# Reader.net
KiCad netlist of a schematic drawn in Altium Designer
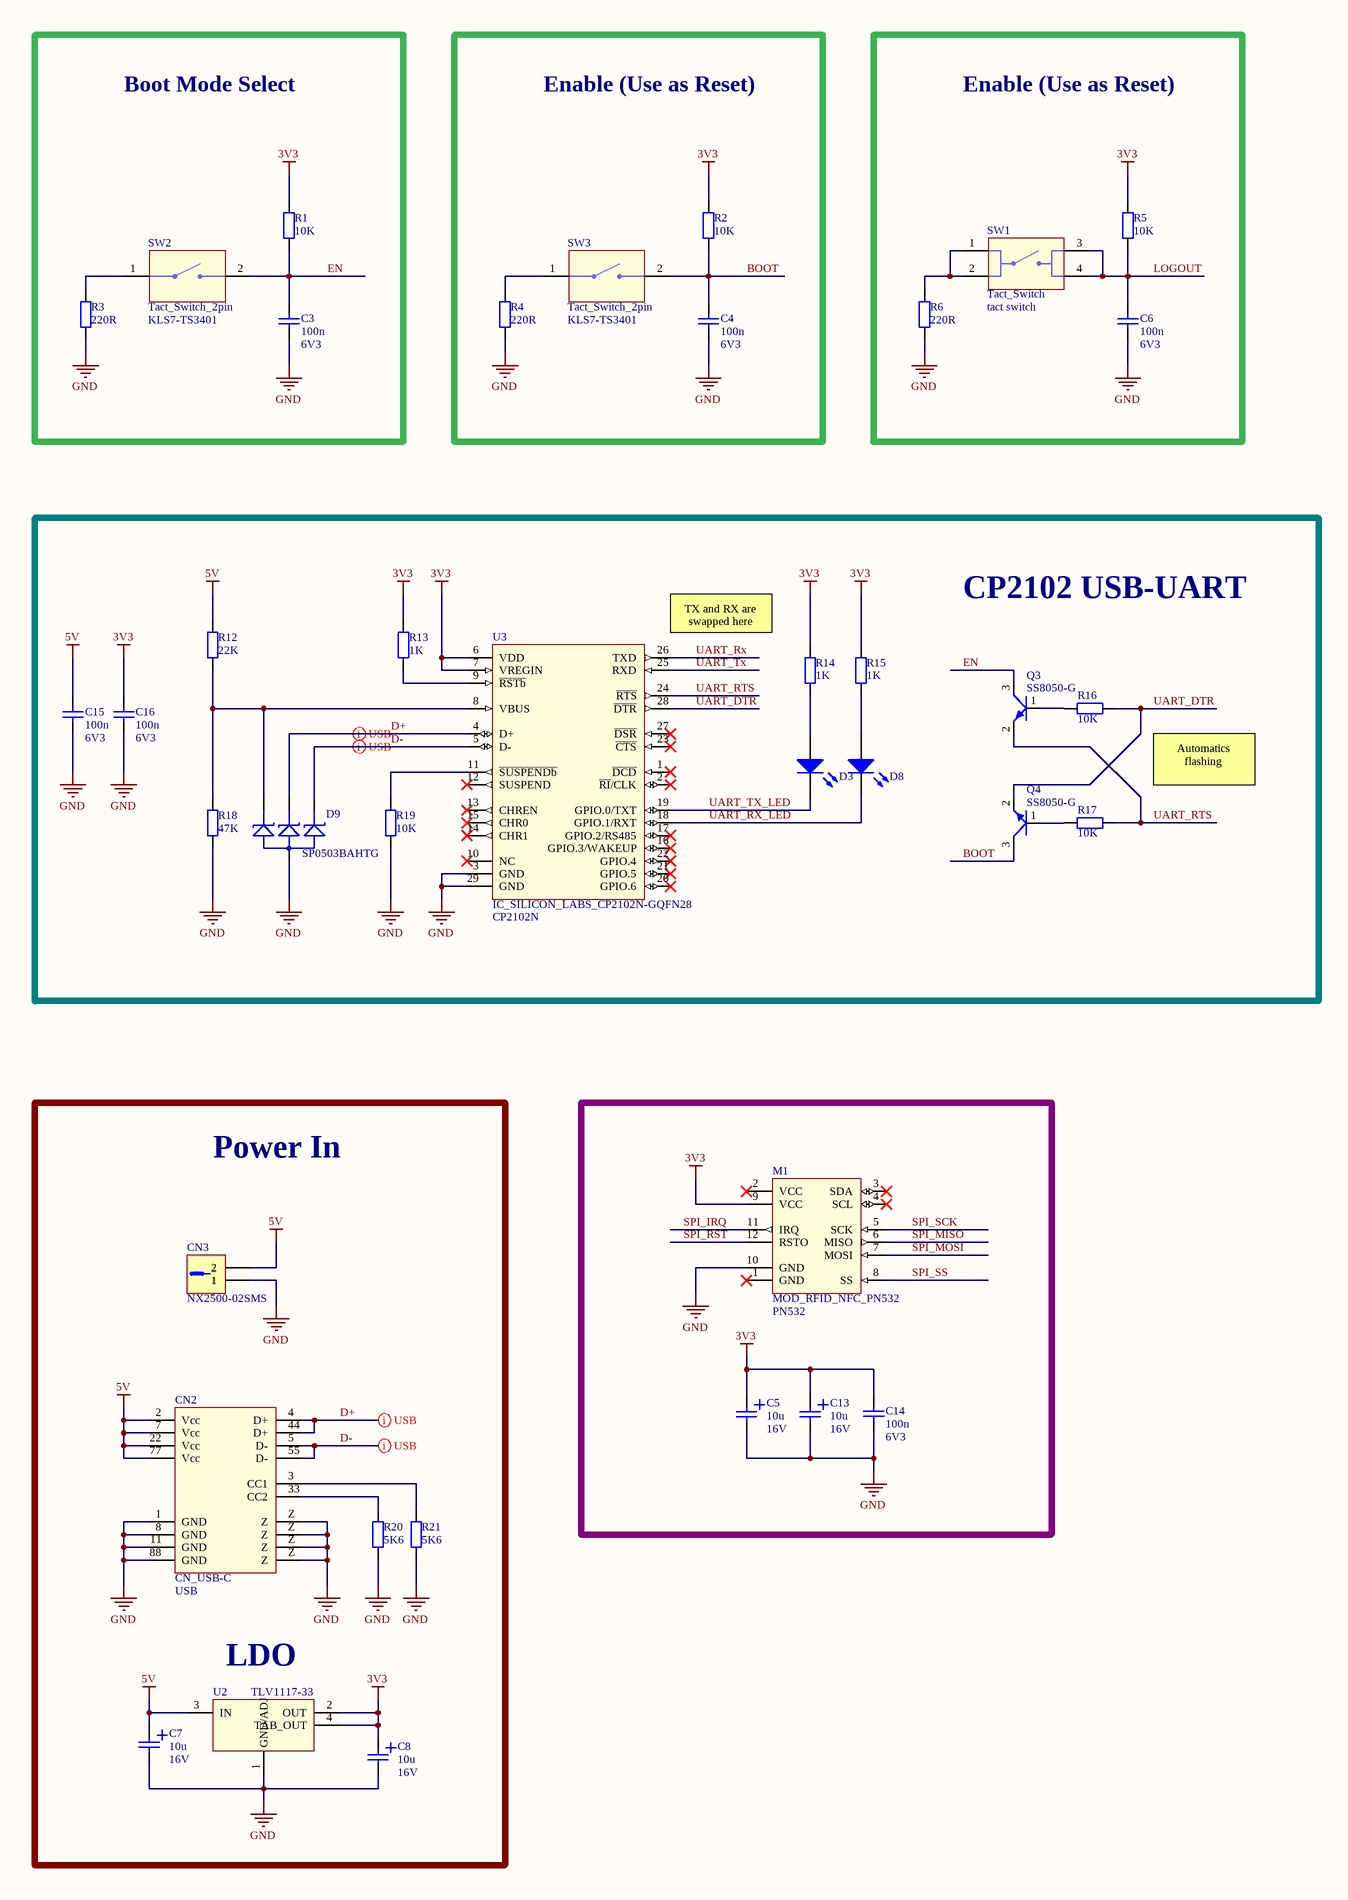
[diagram p0: Reader.SchDoc, left]
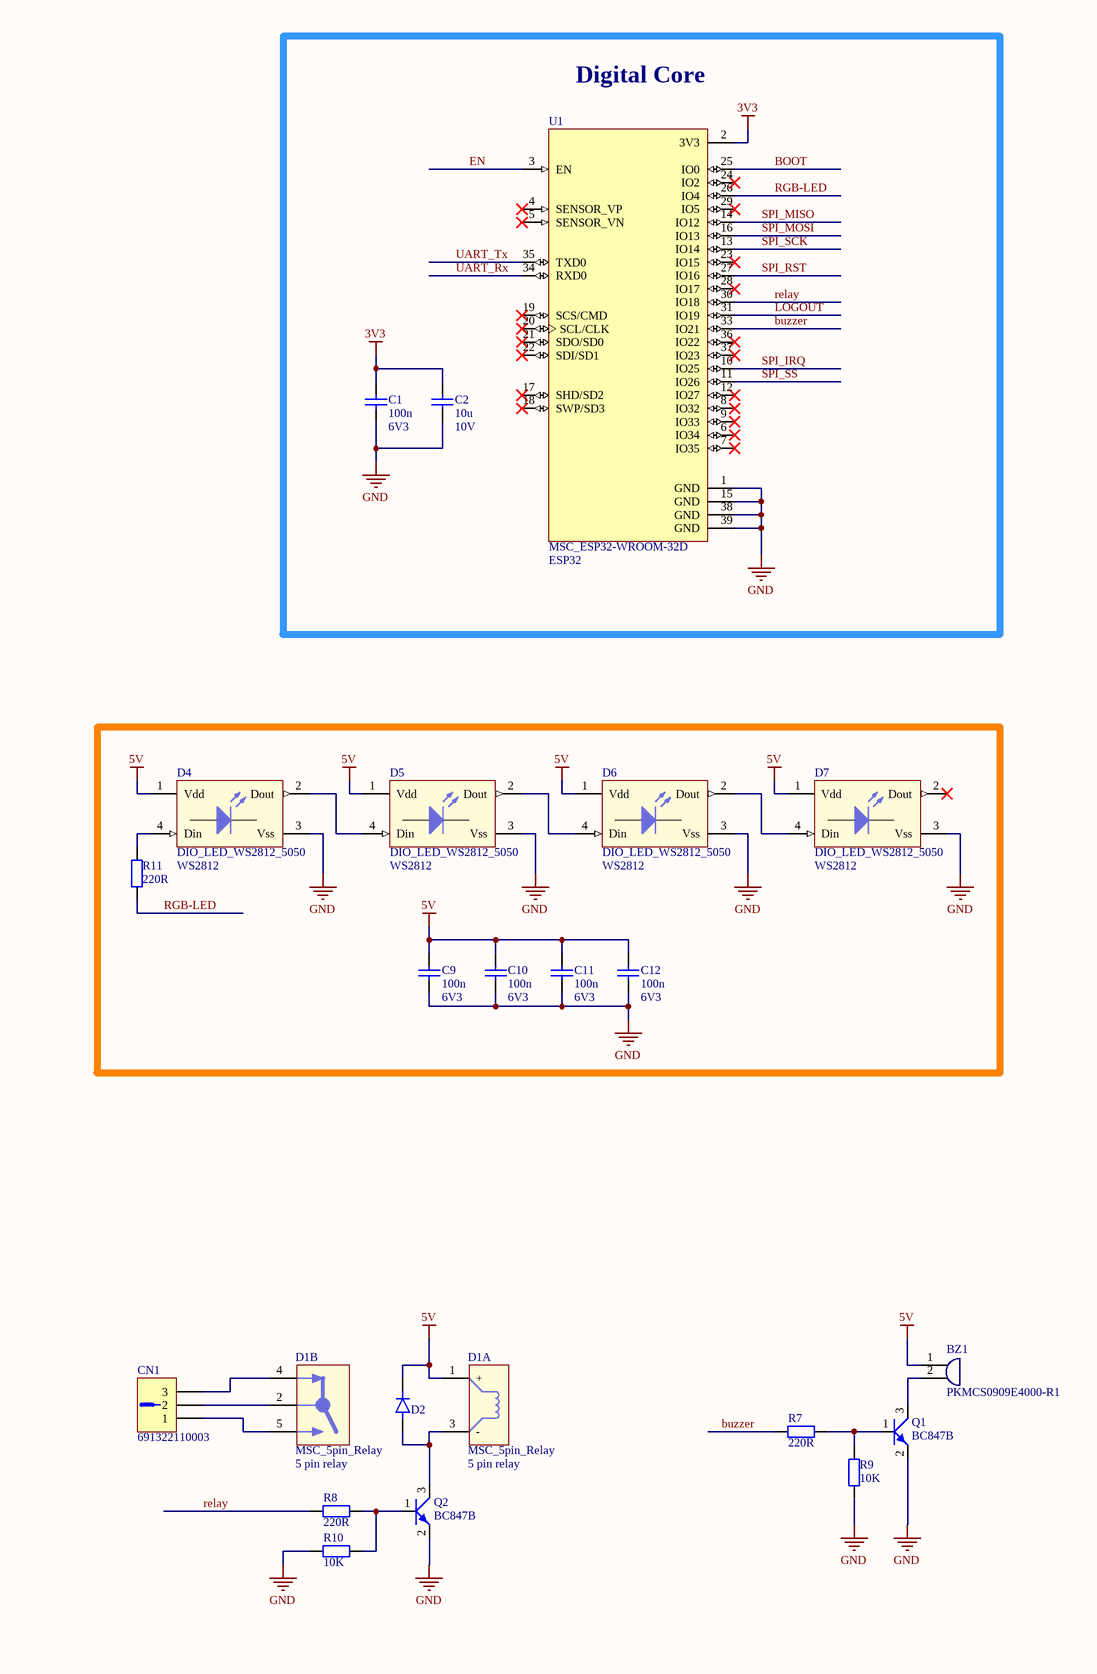
[diagram p1: Reader.SchDoc, right]

(export (version "E")
  (design (tool "Eeschema 10.0.6"))
  (components
    (comp (ref "BZ1")
      (value "MSC_BUZZER")
      (footprint "MSC_MURATA_PKMCS0909E4000-R1")
      (description "Piezo Buzzers & Audio Indicators 65 DB 4.0 KHZ")
      (fields (field (name "VALUE1") "PKMCS0909E4000-R1"))
      (libsource (lib "DSW_Lib") (part "MSC_BUZZER"))
    )
    (comp (ref "C1")
      (value "CAP")
      (footprint "CAPC1608X87N")
      (description "X7R 10% 0603")
      (fields
        (field (name "VALUE1") "100n")
        (field (name "VALUE2") "6V3")
        (field (name "MANUFACTURER") "KEMET")
      )
      (libsource (lib "DSW_Lib") (part "CAP"))
    )
    (comp (ref "C2")
      (value "CAP")
      (footprint "CAPC1608X87N")
      (description "X7R 10% 0603")
      (fields
        (field (name "VALUE1") "10u")
        (field (name "VALUE2") "10V")
        (field (name "MANUFACTURER") "TAIYO YUDEN")
      )
      (libsource (lib "DSW_Lib") (part "CAP"))
    )
    (comp (ref "C3")
      (value "CAP")
      (footprint "CAPC1608X87N")
      (description "X7R 10% 0603")
      (fields
        (field (name "VALUE1") "100n")
        (field (name "VALUE2") "6V3")
        (field (name "MANUFACTURER") "KEMET")
      )
      (libsource (lib "DSW_Lib") (part "CAP"))
    )
    (comp (ref "C4")
      (value "CAP")
      (footprint "CAPC1608X87N")
      (description "X7R 10% 0603")
      (fields
        (field (name "VALUE1") "100n")
        (field (name "VALUE2") "6V3")
        (field (name "MANUFACTURER") "KEMET")
      )
      (libsource (lib "DSW_Lib") (part "CAP"))
    )
    (comp (ref "C5")
      (value "CAP_POL")
      (footprint "CAPM3528x210_N")
      (description "Tantalum, 10%, 3225")
      (fields (field (name "VALUE1") "10u") (field (name "VALUE2") "16V") (field (name "MANUFACTURER") "AVX"))
      (libsource (lib "DSW_Lib") (part "CAP_POL"))
    )
    (comp (ref "C6")
      (value "CAP")
      (footprint "CAPC1608X87N")
      (description "X7R 10% 0603")
      (fields
        (field (name "VALUE1") "100n")
        (field (name "VALUE2") "6V3")
        (field (name "MANUFACTURER") "KEMET")
      )
      (libsource (lib "DSW_Lib") (part "CAP"))
    )
    (comp (ref "C7")
      (value "CAP_POL")
      (footprint "CAPM3528x210_N")
      (description "Tantalum, 10%, 3225")
      (fields (field (name "VALUE1") "10u") (field (name "VALUE2") "16V") (field (name "MANUFACTURER") "AVX"))
      (libsource (lib "DSW_Lib") (part "CAP_POL"))
    )
    (comp (ref "C8")
      (value "CAP_POL")
      (footprint "CAPM3528x210_N")
      (description "Tantalum, 10%, 3225")
      (fields (field (name "VALUE1") "10u") (field (name "VALUE2") "16V") (field (name "MANUFACTURER") "AVX"))
      (libsource (lib "DSW_Lib") (part "CAP_POL"))
    )
    (comp (ref "C9")
      (value "CAP")
      (footprint "CAPC1608X87N")
      (description "X7R 10% 0603")
      (fields
        (field (name "VALUE1") "100n")
        (field (name "VALUE2") "6V3")
        (field (name "MANUFACTURER") "KEMET")
      )
      (libsource (lib "DSW_Lib") (part "CAP"))
    )
    (comp (ref "C10")
      (value "CAP")
      (footprint "CAPC1608X87N")
      (description "X7R 10% 0603")
      (fields
        (field (name "VALUE1") "100n")
        (field (name "VALUE2") "6V3")
        (field (name "MANUFACTURER") "KEMET")
      )
      (libsource (lib "DSW_Lib") (part "CAP"))
    )
    (comp (ref "C11")
      (value "CAP")
      (footprint "CAPC1608X87N")
      (description "X7R 10% 0603")
      (fields
        (field (name "VALUE1") "100n")
        (field (name "VALUE2") "6V3")
        (field (name "MANUFACTURER") "KEMET")
      )
      (libsource (lib "DSW_Lib") (part "CAP"))
    )
    (comp (ref "C12")
      (value "CAP")
      (footprint "CAPC1608X87N")
      (description "X7R 10% 0603")
      (fields
        (field (name "VALUE1") "100n")
        (field (name "VALUE2") "6V3")
        (field (name "MANUFACTURER") "KEMET")
      )
      (libsource (lib "DSW_Lib") (part "CAP"))
    )
    (comp (ref "C13")
      (value "CAP_POL")
      (footprint "CAPM3528x210_N")
      (description "Tantalum, 10%, 3225")
      (fields (field (name "VALUE1") "10u") (field (name "VALUE2") "16V") (field (name "MANUFACTURER") "AVX"))
      (libsource (lib "DSW_Lib") (part "CAP_POL"))
    )
    (comp (ref "C14")
      (value "CAP")
      (footprint "CAPC1608X87N")
      (description "X7R 10% 0603")
      (fields
        (field (name "VALUE1") "100n")
        (field (name "VALUE2") "6V3")
        (field (name "MANUFACTURER") "KEMET")
      )
      (libsource (lib "DSW_Lib") (part "CAP"))
    )
    (comp (ref "C15")
      (value "CAP")
      (footprint "CAPC1608X87N")
      (description "X7R 10% 0603")
      (fields
        (field (name "VALUE1") "100n")
        (field (name "VALUE2") "6V3")
        (field (name "MANUFACTURER") "KEMET")
      )
      (libsource (lib "DSW_Lib") (part "CAP"))
    )
    (comp (ref "C16")
      (value "CAP")
      (footprint "CAPC1608X87N")
      (description "X7R 10% 0603")
      (fields
        (field (name "VALUE1") "100n")
        (field (name "VALUE2") "6V3")
        (field (name "MANUFACTURER") "KEMET")
      )
      (libsource (lib "DSW_Lib") (part "CAP"))
    )
    (comp (ref "CN1")
      (value "CN_1X3M")
      (footprint "CN_Wurth_691322110003")
      (description "Pluggable Terminal Blocks WR-TBL 300VAC 10A 3P Right Angle")
      (fields (field (name "VALUE1") "691322110003") (field (name "MANUFACTURER") "Wurth"))
      (libsource (lib "DSW_Lib") (part "CN_1X3M"))
    )
    (comp (ref "CN2")
      (value "CN_USB-C")
      (footprint "CN_USB-C_vertical")
      (fields (field (name "VALUE1") "USB"))
      (libsource (lib "DSW_Lib") (part "CN_USB-C"))
    )
    (comp (ref "CN3")
      (value "CN_1X2M")
      (footprint "CN_XH2.54-2P-MALE")
      (fields (field (name "VALUE1") "NX2500-02SMS") (field (name "MANUFACTURER") "Joint Tech"))
      (libsource (lib "DSW_Lib") (part "CN_1X2M"))
    )
    (comp (ref "D1")
      (value "MSC_5pin_Relay")
      (footprint "MSC_SRD-12VDC-SL-C")
      (fields (field (name "VALUE1") "5 pin relay") (field (name "MANUFACTURER") "SRD"))
      (libsource (lib "DSW_Lib") (part "MSC_5pin_Relay"))
    )
    (comp (ref "D2")
      (value "DIO")
      (footprint "DO-214AC")
      (libsource (lib "Mixer_Motherboard") (part "DIO_SS16"))
    )
    (comp (ref "D3")
      (value "DIO_LED")
      (footprint "DIO_RED_0603")
      (description "Standard LEDs - SMD WL-SMCW SMDMono TpVw Waterclr 0603 Red")
      (fields (field (name "MANUFACTURER") "Wurth Electronics"))
      (libsource (lib "DSW_Lib") (part "DIO_LED"))
    )
    (comp (ref "D4")
      (value "DIO_LED_WS2812_5050")
      (footprint "DIO_LED_WORLDSEMI_WS2812B")
      (description "RGB 5050 address")
      (fields (field (name "VALUE1") "WS2812") (field (name "MANUFACTURER") "WORLDSEMI"))
      (libsource (lib "DSW_Lib") (part "DIO_LED_WS2812_5050"))
    )
    (comp (ref "D5")
      (value "DIO_LED_WS2812_5050")
      (footprint "DIO_LED_WORLDSEMI_WS2812B")
      (description "RGB 5050 address")
      (fields (field (name "VALUE1") "WS2812") (field (name "MANUFACTURER") "WORLDSEMI"))
      (libsource (lib "DSW_Lib") (part "DIO_LED_WS2812_5050"))
    )
    (comp (ref "D6")
      (value "DIO_LED_WS2812_5050")
      (footprint "DIO_LED_WORLDSEMI_WS2812B")
      (description "RGB 5050 address")
      (fields (field (name "VALUE1") "WS2812") (field (name "MANUFACTURER") "WORLDSEMI"))
      (libsource (lib "DSW_Lib") (part "DIO_LED_WS2812_5050"))
    )
    (comp (ref "D7")
      (value "DIO_LED_WS2812_5050")
      (footprint "DIO_LED_WORLDSEMI_WS2812B")
      (description "RGB 5050 address")
      (fields (field (name "VALUE1") "WS2812") (field (name "MANUFACTURER") "WORLDSEMI"))
      (libsource (lib "DSW_Lib") (part "DIO_LED_WS2812_5050"))
    )
    (comp (ref "D8")
      (value "DIO_LED")
      (footprint "DIO_RED_0603")
      (description "Standard LEDs - SMD WL-SMCW SMDMono TpVw Waterclr 0603 Red")
      (fields (field (name "MANUFACTURER") "Wurth Electronics"))
      (libsource (lib "DSW_Lib") (part "DIO_LED"))
    )
    (comp (ref "D9")
      (value "DIO_TVS_THREE")
      (footprint "SOT143-L")
      (description "ESD Suppressors / TVS Diodes TVS AVAL DIODE SMT")
      (fields (field (name "VALUE1") "SP0503BAHTG") (field (name "MANUFACTURER") "Littelfuse"))
      (libsource (lib "DSW_Lib") (part "DIO_TVS_THREE"))
    )
    (comp (ref "M1")
      (value "MOD_RFID_NFC_PN532")
      (footprint "MOD_RFID_NFC_PN532_no3d")
      (fields (field (name "VALUE1") "PN532"))
      (libsource (lib "DSW_Lib") (part "MOD_RFID_NFC_PN532"))
    )
    (comp (ref "Q1")
      (value "TRS_NPN_123")
      (footprint "SOT23")
      (description "Bipolar Transistors - BJT NPN 45V 100mA")
      (fields (field (name "VALUE1") "BC847B") (field (name "MANUFACTURER") "NXP"))
      (libsource (lib "DSW_Lib") (part "TRS_NPN_123"))
    )
    (comp (ref "Q2")
      (value "TRS_NPN_123")
      (footprint "SOT23")
      (description "Bipolar Transistors - BJT NPN 45V 100mA")
      (fields (field (name "VALUE1") "BC847B") (field (name "MANUFACTURER") "NXP"))
      (libsource (lib "DSW_Lib") (part "TRS_NPN_123"))
    )
    (comp (ref "Q3")
      (value "TRS_NPN_123")
      (footprint "SOT23")
      (description "Bipolar Transistors - BJT NPN TRANSISTOR 1.5A 40V")
      (fields (field (name "VALUE1") "SS8050-G") (field (name "MANUFACTURER") "Comchip"))
      (libsource (lib "DSW_Lib") (part "TRS_NPN_123"))
    )
    (comp (ref "Q4")
      (value "TRS_NPN_123")
      (footprint "SOT23")
      (description "Bipolar Transistors - BJT NPN TRANSISTOR 1.5A 40V")
      (fields (field (name "VALUE1") "SS8050-G") (field (name "MANUFACTURER") "Comchip"))
      (libsource (lib "DSW_Lib") (part "TRS_NPN_123"))
    )
    (comp (ref "R1")
      (value "RES")
      (footprint "RESC1608X55N")
      (description "RESISTOR, 0603, 01K, 1%, SMD")
      (fields (field (name "VALUE1") "10K") (field (name "MANUFACTURER") "Yageo"))
      (libsource (lib "DSW_Lib") (part "RES"))
    )
    (comp (ref "R2")
      (value "RES")
      (footprint "RESC1608X55N")
      (description "RESISTOR, 0603, 01K, 1%, SMD")
      (fields (field (name "VALUE1") "10K") (field (name "MANUFACTURER") "Yageo"))
      (libsource (lib "DSW_Lib") (part "RES"))
    )
    (comp (ref "R3")
      (value "RES")
      (footprint "RESC1608X55N")
      (description "RESISTOR, 0603, 220R, 1%, SMD")
      (fields (field (name "VALUE1") "220R") (field (name "MANUFACTURER") "Yageo"))
      (libsource (lib "DSW_Lib") (part "RES"))
    )
    (comp (ref "R4")
      (value "RES")
      (footprint "RESC1608X55N")
      (description "RESISTOR, 0603, 220R, 1%, SMD")
      (fields (field (name "VALUE1") "220R") (field (name "MANUFACTURER") "Yageo"))
      (libsource (lib "DSW_Lib") (part "RES"))
    )
    (comp (ref "R5")
      (value "RES")
      (footprint "RESC1608X55N")
      (description "RESISTOR, 0603, 01K, 1%, SMD")
      (fields (field (name "VALUE1") "10K") (field (name "MANUFACTURER") "Yageo"))
      (libsource (lib "DSW_Lib") (part "RES"))
    )
    (comp (ref "R6")
      (value "RES")
      (footprint "RESC1608X55N")
      (description "RESISTOR, 0603, 220R, 1%, SMD")
      (fields (field (name "VALUE1") "220R") (field (name "MANUFACTURER") "Yageo"))
      (libsource (lib "DSW_Lib") (part "RES"))
    )
    (comp (ref "R7")
      (value "RES")
      (footprint "RESC1608X55N")
      (description "RESISTOR, 0603, 220R, 1%, SMD")
      (fields (field (name "VALUE1") "220R") (field (name "MANUFACTURER") "Yageo"))
      (libsource (lib "") (part "RES_1"))
    )
    (comp (ref "R8")
      (value "RES")
      (footprint "RESC1608X55N")
      (description "RESISTOR, 0603, 220R, 1%, SMD")
      (fields (field (name "VALUE1") "220R") (field (name "MANUFACTURER") "Yageo"))
      (libsource (lib "") (part "RES_1"))
    )
    (comp (ref "R9")
      (value "RES")
      (footprint "RESC1608X55N")
      (description "RESISTOR, 0603, 01K, 1%, SMD")
      (fields (field (name "VALUE1") "10K") (field (name "MANUFACTURER") "Yageo"))
      (libsource (lib "") (part "RES_1"))
    )
    (comp (ref "R10")
      (value "RES")
      (footprint "RESC1608X55N")
      (description "RESISTOR, 0603, 01K, 1%, SMD")
      (fields (field (name "VALUE1") "10K") (field (name "MANUFACTURER") "Yageo"))
      (libsource (lib "") (part "RES_1"))
    )
    (comp (ref "R11")
      (value "RES")
      (footprint "RESC1608X55N")
      (description "RESISTOR, 0603, 220R, 1%, SMD")
      (fields (field (name "VALUE1") "220R") (field (name "MANUFACTURER") "Yageo"))
      (libsource (lib "DSW_Lib") (part "RES"))
    )
    (comp (ref "R12")
      (value "RES")
      (footprint "RESC1608X55N")
      (description "RESISTOR, 0603, 22K, 1%, SMD")
      (fields (field (name "VALUE1") "22K") (field (name "MANUFACTURER") "Yageo"))
      (libsource (lib "DSW_Lib") (part "RES"))
    )
    (comp (ref "R13")
      (value "RES")
      (footprint "RESC1608X55N")
      (description "RESISTOR, 0603, 1K, 1%, SMD")
      (fields (field (name "VALUE1") "1K") (field (name "MANUFACTURER") "Yageo"))
      (libsource (lib "DSW_Lib") (part "RES"))
    )
    (comp (ref "R14")
      (value "RES")
      (footprint "RESC1608X55N")
      (description "RESISTOR, 0603, 1K, 1%, SMD")
      (fields (field (name "VALUE1") "1K") (field (name "MANUFACTURER") "Yageo"))
      (libsource (lib "DSW_Lib") (part "RES"))
    )
    (comp (ref "R15")
      (value "RES")
      (footprint "RESC1608X55N")
      (description "RESISTOR, 0603, 1K, 1%, SMD")
      (fields (field (name "VALUE1") "1K") (field (name "MANUFACTURER") "Yageo"))
      (libsource (lib "DSW_Lib") (part "RES"))
    )
    (comp (ref "R16")
      (value "RES")
      (footprint "RESC1608X55N")
      (description "RESISTOR, 0603, 01K, 1%, SMD")
      (fields (field (name "VALUE1") "10K") (field (name "MANUFACTURER") "Yageo"))
      (libsource (lib "") (part "RES_2"))
    )
    (comp (ref "R17")
      (value "RES")
      (footprint "RESC1608X55N")
      (description "RESISTOR, 0603, 01K, 1%, SMD")
      (fields (field (name "VALUE1") "10K") (field (name "MANUFACTURER") "Yageo"))
      (libsource (lib "") (part "RES_2"))
    )
    (comp (ref "R18")
      (value "RES")
      (footprint "RESC1608X55N")
      (description "RESISTOR, 0603, 47K, 1%, SMD")
      (fields (field (name "VALUE1") "47K") (field (name "MANUFACTURER") "Yageo"))
      (libsource (lib "DSW_Lib") (part "RES"))
    )
    (comp (ref "R19")
      (value "RES")
      (footprint "RESC1608X55N")
      (description "RESISTOR, 0603, 01K, 1%, SMD")
      (fields (field (name "VALUE1") "10K") (field (name "MANUFACTURER") "Yageo"))
      (libsource (lib "DSW_Lib") (part "RES"))
    )
    (comp (ref "R20")
      (value "RES")
      (footprint "RESC1608X55N")
      (description "RESISTOR, 0603, 5K6, 1%, SMD")
      (fields (field (name "VALUE1") "5K6") (field (name "MANUFACTURER") "Yageo"))
      (libsource (lib "DSW_Lib") (part "RES"))
    )
    (comp (ref "R21")
      (value "RES")
      (footprint "RESC1608X55N")
      (description "RESISTOR, 0603, 5K6, 1%, SMD")
      (fields (field (name "VALUE1") "5K6") (field (name "MANUFACTURER") "Yageo"))
      (libsource (lib "DSW_Lib") (part "RES"))
    )
    (comp (ref "SW1")
      (value "Tact_Switch")
      (footprint "Tact_Switch_SMD")
      (fields (field (name "VALUE1") "tact switch"))
      (libsource (lib "DSW_Lib") (part "Tact_Switch"))
    )
    (comp (ref "SW2")
      (value "Tact_Switch_2pin")
      (footprint "MSC_KLS7-TS3401")
      (description "Tactile switch SMD")
      (fields (field (name "VALUE1") "KLS7-TS3401") (field (name "MANUFACTURER") "KLS"))
      (libsource (lib "DSW_Lib") (part "Tact_Switch_2pin"))
    )
    (comp (ref "SW3")
      (value "Tact_Switch_2pin")
      (footprint "MSC_KLS7-TS3401")
      (description "Tactile switch SMD")
      (fields (field (name "VALUE1") "KLS7-TS3401") (field (name "MANUFACTURER") "KLS"))
      (libsource (lib "DSW_Lib") (part "Tact_Switch_2pin"))
    )
    (comp (ref "U1")
      (value "MSC_ESP32-WROOM-32D")
      (footprint "MSC_ESP32-WROOM-32D")
      (fields (field (name "VALUE1") "ESP32") (field (name "MANUFACTURER") "Espressif"))
      (libsource (lib "DSW_Lib") (part "MSC_ESP32-WROOM-32D"))
    )
    (comp (ref "U2")
      (value "IC_TI_LM1117")
      (footprint "SOT230P730X180-4N")
      (description "IC, LDO VOLT REG, 3V3, 0.8A, SOT-223-4")
      (fields (field (name "VALUE1") "TLV1117-33") (field (name "MANUFACTURER") "Texas Instruments"))
      (libsource (lib "DSW_Lib") (part "IC_TI_LM1117"))
    )
    (comp (ref "U3")
      (value "IC_SILICON_LABS_CP2102N-GQFN28")
      (footprint "QFN-28N")
      (description "USB Interface IC USBXpress - USB to UART Bridge QFN28")
      (fields (field (name "VALUE1") "CP2102N") (field (name "MANUFACTURER") "Silicon Labs"))
      (libsource (lib "DSW_Lib") (part "IC_SILICON_LABS_CP2102N-GQFN28"))
    )
  )
  (nets
    (net (code "1") (name "/BOOT") (class "Default")
      (node (ref "C4") (pin "2") (pinfunction "2_2") (pintype "passive"))
      (node (ref "Q4") (pin "3") (pinfunction "C_3") (pintype "passive"))
      (node (ref "R2") (pin "1") (pinfunction "1_1") (pintype "passive"))
      (node (ref "SW3") (pin "2") (pinfunction "2_2") (pintype "passive"))
      (node (ref "U1") (pin "25") (pinfunction "IO0_25") (pintype "bidirectional"))
    )
    (net (code "2") (name "/D+") (class "Default")
      (node (ref "CN2") (pin "4") (pinfunction "D+_4") (pintype "passive"))
      (node (ref "CN2") (pin "44") (pinfunction "D+_44") (pintype "passive"))
      (node (ref "D9") (pin "3") (pinfunction "Cathode_3") (pintype "passive"))
      (node (ref "U3") (pin "4") (pinfunction "D+_4") (pintype "bidirectional"))
    )
    (net (code "3") (name "/D-") (class "Default")
      (node (ref "CN2") (pin "5") (pinfunction "D-_5") (pintype "passive"))
      (node (ref "CN2") (pin "55") (pinfunction "D-_55") (pintype "passive"))
      (node (ref "D9") (pin "4") (pinfunction "Cathode_4") (pintype "passive"))
      (node (ref "U3") (pin "5") (pinfunction "D-_5") (pintype "bidirectional"))
    )
    (net (code "4") (name "/EN") (class "Default")
      (node (ref "C3") (pin "2") (pinfunction "2_2") (pintype "passive"))
      (node (ref "Q3") (pin "3") (pinfunction "C_3") (pintype "passive"))
      (node (ref "R1") (pin "1") (pinfunction "1_1") (pintype "passive"))
      (node (ref "SW2") (pin "2") (pinfunction "2_2") (pintype "passive"))
      (node (ref "U1") (pin "3") (pinfunction "EN_3") (pintype "input"))
    )
    (net (code "5") (name "/LOGOUT") (class "Default")
      (node (ref "C6") (pin "2") (pinfunction "2_2") (pintype "passive"))
      (node (ref "R5") (pin "1") (pinfunction "1_1") (pintype "passive"))
      (node (ref "SW1") (pin "3") (pinfunction "3_3") (pintype "passive"))
      (node (ref "SW1") (pin "4") (pinfunction "4_4") (pintype "passive"))
      (node (ref "U1") (pin "31") (pinfunction "IO19_31") (pintype "bidirectional"))
    )
    (net (code "6") (name "/RGB-LED") (class "Default")
      (node (ref "R11") (pin "1") (pinfunction "1_1") (pintype "passive"))
      (node (ref "U1") (pin "26") (pinfunction "IO4_26") (pintype "bidirectional"))
    )
    (net (code "7") (name "/SPI_IRQ") (class "Default")
      (node (ref "M1") (pin "11") (pinfunction "IRQ_11") (pintype "output"))
      (node (ref "U1") (pin "10") (pinfunction "IO25_10") (pintype "bidirectional"))
    )
    (net (code "8") (name "/SPI_MISO") (class "Default")
      (node (ref "M1") (pin "6") (pinfunction "MISO_6") (pintype "output"))
      (node (ref "U1") (pin "14") (pinfunction "IO12_14") (pintype "bidirectional"))
    )
    (net (code "9") (name "/SPI_MOSI") (class "Default")
      (node (ref "M1") (pin "7") (pinfunction "MOSI_7") (pintype "input"))
      (node (ref "U1") (pin "16") (pinfunction "IO13_16") (pintype "bidirectional"))
    )
    (net (code "10") (name "/SPI_RST") (class "Default")
      (node (ref "M1") (pin "12") (pinfunction "RSTO_12") (pintype "passive"))
      (node (ref "U1") (pin "27") (pinfunction "IO16_27") (pintype "bidirectional"))
    )
    (net (code "11") (name "/SPI_SCK") (class "Default")
      (node (ref "M1") (pin "5") (pinfunction "SCK_5") (pintype "input"))
      (node (ref "U1") (pin "13") (pinfunction "IO14_13") (pintype "bidirectional"))
    )
    (net (code "12") (name "/SPI_SS") (class "Default")
      (node (ref "M1") (pin "8") (pinfunction "SS_8") (pintype "input"))
      (node (ref "U1") (pin "11") (pinfunction "IO26_11") (pintype "bidirectional"))
    )
    (net (code "13") (name "/UART_DTR") (class "Default")
      (node (ref "Q4") (pin "2") (pinfunction "E_2") (pintype "passive"))
      (node (ref "R16") (pin "1") (pinfunction "1_1") (pintype "passive"))
      (node (ref "U3") (pin "28") (pinfunction "~{DTR}_28") (pintype "output"))
    )
    (net (code "14") (name "/UART_RTS") (class "Default")
      (node (ref "Q3") (pin "2") (pinfunction "E_2") (pintype "passive"))
      (node (ref "R17") (pin "1") (pinfunction "1_1") (pintype "passive"))
      (node (ref "U3") (pin "24") (pinfunction "~{RTS}_24") (pintype "output"))
    )
    (net (code "15") (name "/UART_RX_LED") (class "Default")
      (node (ref "D8") (pin "1") (pinfunction "K_1") (pintype "passive"))
      (node (ref "U3") (pin "18") (pinfunction "GPIO.1/RXT_18") (pintype "bidirectional"))
    )
    (net (code "16") (name "/UART_Rx") (class "Default")
      (node (ref "U1") (pin "34") (pinfunction "RXD0_34") (pintype "bidirectional"))
      (node (ref "U3") (pin "26") (pinfunction "TXD_26") (pintype "output"))
    )
    (net (code "17") (name "/UART_TX_LED") (class "Default")
      (node (ref "D3") (pin "1") (pinfunction "K_1") (pintype "passive"))
      (node (ref "U3") (pin "19") (pinfunction "GPIO.0/TXT_19") (pintype "bidirectional"))
    )
    (net (code "18") (name "/UART_Tx") (class "Default")
      (node (ref "U1") (pin "35") (pinfunction "TXD0_35") (pintype "bidirectional"))
      (node (ref "U3") (pin "25") (pinfunction "RXD_25") (pintype "input"))
    )
    (net (code "19") (name "/buzzer") (class "Default")
      (node (ref "R7") (pin "1") (pinfunction "1_1") (pintype "passive"))
      (node (ref "U1") (pin "33") (pinfunction "IO21_33") (pintype "bidirectional"))
    )
    (net (code "20") (name "/relay") (class "Default")
      (node (ref "R8") (pin "1") (pinfunction "1_1") (pintype "passive"))
      (node (ref "U1") (pin "30") (pinfunction "IO18_30") (pintype "bidirectional"))
    )
    (net (code "21") (name "3V3") (class "Default")
      (node (ref "C1") (pin "2") (pinfunction "2_2") (pintype "passive"))
      (node (ref "C13") (pin "1") (pinfunction "1_1") (pintype "passive"))
      (node (ref "C14") (pin "2") (pinfunction "2_2") (pintype "passive"))
      (node (ref "C16") (pin "2") (pinfunction "2_2") (pintype "passive"))
      (node (ref "C2") (pin "2") (pinfunction "2_2") (pintype "passive"))
      (node (ref "C5") (pin "1") (pinfunction "1_1") (pintype "passive"))
      (node (ref "C8") (pin "1") (pinfunction "1_1") (pintype "passive"))
      (node (ref "M1") (pin "9") (pinfunction "VCC_9") (pintype "power_in"))
      (node (ref "R1") (pin "2") (pinfunction "2_2") (pintype "passive"))
      (node (ref "R13") (pin "2") (pinfunction "2_2") (pintype "passive"))
      (node (ref "R14") (pin "2") (pinfunction "2_2") (pintype "passive"))
      (node (ref "R15") (pin "2") (pinfunction "2_2") (pintype "passive"))
      (node (ref "R2") (pin "2") (pinfunction "2_2") (pintype "passive"))
      (node (ref "R5") (pin "2") (pinfunction "2_2") (pintype "passive"))
      (node (ref "U1") (pin "2") (pinfunction "3V3_2") (pintype "power_in"))
      (node (ref "U2") (pin "2") (pinfunction "OUT_2") (pintype "passive"))
      (node (ref "U2") (pin "4") (pinfunction "TAB_OUT_4") (pintype "passive"))
      (node (ref "U3") (pin "6") (pinfunction "VDD_6") (pintype "power_in"))
      (node (ref "U3") (pin "7") (pinfunction "VREGIN_7") (pintype "input"))
    )
    (net (code "22") (name "5V") (class "Default")
      (node (ref "BZ1") (pin "1") (pinfunction "1_1") (pintype "passive"))
      (node (ref "C10") (pin "2") (pinfunction "2_2") (pintype "passive"))
      (node (ref "C11") (pin "2") (pinfunction "2_2") (pintype "passive"))
      (node (ref "C12") (pin "2") (pinfunction "2_2") (pintype "passive"))
      (node (ref "C15") (pin "2") (pinfunction "2_2") (pintype "passive"))
      (node (ref "C7") (pin "1") (pinfunction "1_1") (pintype "passive"))
      (node (ref "C9") (pin "2") (pinfunction "2_2") (pintype "passive"))
      (node (ref "CN2") (pin "2") (pinfunction "Vcc_2") (pintype "passive"))
      (node (ref "CN2") (pin "22") (pinfunction "Vcc_22") (pintype "passive"))
      (node (ref "CN2") (pin "7") (pinfunction "Vcc_7") (pintype "passive"))
      (node (ref "CN2") (pin "77") (pinfunction "Vcc_77") (pintype "passive"))
      (node (ref "CN3") (pin "2") (pinfunction "2_2") (pintype "passive"))
      (node (ref "D1") (pin "1") (pinfunction "+_1") (pintype "power_in"))
      (node (ref "D2") (pin "1") (pinfunction "K_1") (pintype "passive"))
      (node (ref "D4") (pin "1") (pinfunction "Vdd_1") (pintype "power_in"))
      (node (ref "D5") (pin "1") (pinfunction "Vdd_1") (pintype "power_in"))
      (node (ref "D6") (pin "1") (pinfunction "Vdd_1") (pintype "power_in"))
      (node (ref "D7") (pin "1") (pinfunction "Vdd_1") (pintype "power_in"))
      (node (ref "R12") (pin "2") (pinfunction "2_2") (pintype "passive"))
      (node (ref "U2") (pin "3") (pinfunction "IN_3") (pintype "passive"))
    )
    (net (code "23") (name "GND") (class "Default")
      (node (ref "C1") (pin "1") (pinfunction "1_1") (pintype "passive"))
      (node (ref "C10") (pin "1") (pinfunction "1_1") (pintype "passive"))
      (node (ref "C11") (pin "1") (pinfunction "1_1") (pintype "passive"))
      (node (ref "C12") (pin "1") (pinfunction "1_1") (pintype "passive"))
      (node (ref "C13") (pin "2") (pinfunction "2_2") (pintype "passive"))
      (node (ref "C14") (pin "1") (pinfunction "1_1") (pintype "passive"))
      (node (ref "C15") (pin "1") (pinfunction "1_1") (pintype "passive"))
      (node (ref "C16") (pin "1") (pinfunction "1_1") (pintype "passive"))
      (node (ref "C2") (pin "1") (pinfunction "1_1") (pintype "passive"))
      (node (ref "C3") (pin "1") (pinfunction "1_1") (pintype "passive"))
      (node (ref "C4") (pin "1") (pinfunction "1_1") (pintype "passive"))
      (node (ref "C5") (pin "2") (pinfunction "2_2") (pintype "passive"))
      (node (ref "C6") (pin "1") (pinfunction "1_1") (pintype "passive"))
      (node (ref "C7") (pin "2") (pinfunction "2_2") (pintype "passive"))
      (node (ref "C8") (pin "2") (pinfunction "2_2") (pintype "passive"))
      (node (ref "C9") (pin "1") (pinfunction "1_1") (pintype "passive"))
      (node (ref "CN2") (pin "1") (pinfunction "GND_1") (pintype "passive"))
      (node (ref "CN2") (pin "11") (pinfunction "GND_11") (pintype "passive"))
      (node (ref "CN2") (pin "8") (pinfunction "GND_8") (pintype "passive"))
      (node (ref "CN2") (pin "88") (pinfunction "GND_88") (pintype "passive"))
      (node (ref "CN2") (pin "Z") (pinfunction "Z_Z") (pintype "passive"))
      (node (ref "CN3") (pin "1") (pinfunction "1_1") (pintype "passive"))
      (node (ref "D4") (pin "3") (pinfunction "Vss_3") (pintype "power_in"))
      (node (ref "D5") (pin "3") (pinfunction "Vss_3") (pintype "power_in"))
      (node (ref "D6") (pin "3") (pinfunction "Vss_3") (pintype "power_in"))
      (node (ref "D7") (pin "3") (pinfunction "Vss_3") (pintype "power_in"))
      (node (ref "D9") (pin "1") (pinfunction "Anode_1") (pintype "passive"))
      (node (ref "M1") (pin "10") (pinfunction "GND_10") (pintype "power_in"))
      (node (ref "Q1") (pin "2") (pinfunction "E_2") (pintype "passive"))
      (node (ref "Q2") (pin "2") (pinfunction "E_2") (pintype "passive"))
      (node (ref "R10") (pin "1") (pinfunction "1_1") (pintype "passive"))
      (node (ref "R18") (pin "1") (pinfunction "1_1") (pintype "passive"))
      (node (ref "R19") (pin "1") (pinfunction "1_1") (pintype "passive"))
      (node (ref "R20") (pin "1") (pinfunction "1_1") (pintype "passive"))
      (node (ref "R21") (pin "1") (pinfunction "1_1") (pintype "passive"))
      (node (ref "R3") (pin "1") (pinfunction "1_1") (pintype "passive"))
      (node (ref "R4") (pin "1") (pinfunction "1_1") (pintype "passive"))
      (node (ref "R6") (pin "1") (pinfunction "1_1") (pintype "passive"))
      (node (ref "R9") (pin "1") (pinfunction "1_1") (pintype "passive"))
      (node (ref "U1") (pin "1") (pinfunction "GND_1") (pintype "power_in"))
      (node (ref "U1") (pin "15") (pinfunction "GND_15") (pintype "power_in"))
      (node (ref "U1") (pin "38") (pinfunction "GND_38") (pintype "power_in"))
      (node (ref "U1") (pin "39") (pinfunction "GND_39") (pintype "power_in"))
      (node (ref "U2") (pin "1") (pinfunction "GND/ADJ_1") (pintype "passive"))
      (node (ref "U3") (pin "29") (pinfunction "GND_29") (pintype "power_in"))
      (node (ref "U3") (pin "3") (pinfunction "GND_3") (pintype "power_in"))
    )
    (net (code "24") (name "Net-(CN1-Pad1)") (class "Default")
      (node (ref "CN1") (pin "1") (pinfunction "1_1") (pintype "passive"))
      (node (ref "D1") (pin "5") (pinfunction "5_5") (pintype "power_in"))
    )
    (net (code "25") (name "Net-(CN1-Pad2)") (class "Default")
      (node (ref "CN1") (pin "2") (pinfunction "2_2") (pintype "passive"))
      (node (ref "D1") (pin "2") (pinfunction "2_2") (pintype "power_in"))
    )
    (net (code "26") (name "Net-(CN1-Pad3)") (class "Default")
      (node (ref "CN1") (pin "3") (pinfunction "3_3") (pintype "passive"))
      (node (ref "D1") (pin "4") (pinfunction "4_4") (pintype "power_in"))
    )
    (net (code "27") (name "Net-(CN2-CC1)") (class "Default")
      (node (ref "CN2") (pin "3") (pinfunction "CC1_3") (pintype "passive"))
      (node (ref "R21") (pin "2") (pinfunction "2_2") (pintype "passive"))
    )
    (net (code "28") (name "Net-(CN2-CC2)") (class "Default")
      (node (ref "CN2") (pin "33") (pinfunction "CC2_33") (pintype "passive"))
      (node (ref "R20") (pin "2") (pinfunction "2_2") (pintype "passive"))
    )
    (net (code "29") (name "Net-(D1A--)") (class "Default")
      (node (ref "D1") (pin "3") (pinfunction "-_3") (pintype "power_in"))
      (node (ref "D2") (pin "2") (pinfunction "A_2") (pintype "passive"))
      (node (ref "Q2") (pin "3") (pinfunction "C_3") (pintype "passive"))
    )
    (net (code "30") (name "Net-(D3-A)") (class "Default")
      (node (ref "D3") (pin "2") (pinfunction "A_2") (pintype "passive"))
      (node (ref "R14") (pin "1") (pinfunction "1_1") (pintype "passive"))
    )
    (net (code "31") (name "Net-(D4-Din)") (class "Default")
      (node (ref "D4") (pin "4") (pinfunction "Din_4") (pintype "input"))
      (node (ref "R11") (pin "2") (pinfunction "2_2") (pintype "passive"))
    )
    (net (code "32") (name "Net-(D4-Dout)") (class "Default")
      (node (ref "D4") (pin "2") (pinfunction "Dout_2") (pintype "output"))
      (node (ref "D5") (pin "4") (pinfunction "Din_4") (pintype "input"))
    )
    (net (code "33") (name "Net-(D5-Dout)") (class "Default")
      (node (ref "D5") (pin "2") (pinfunction "Dout_2") (pintype "output"))
      (node (ref "D6") (pin "4") (pinfunction "Din_4") (pintype "input"))
    )
    (net (code "34") (name "Net-(D6-Dout)") (class "Default")
      (node (ref "D6") (pin "2") (pinfunction "Dout_2") (pintype "output"))
      (node (ref "D7") (pin "4") (pinfunction "Din_4") (pintype "input"))
    )
    (net (code "35") (name "Net-(D8-A)") (class "Default")
      (node (ref "D8") (pin "2") (pinfunction "A_2") (pintype "passive"))
      (node (ref "R15") (pin "1") (pinfunction "1_1") (pintype "passive"))
    )
    (net (code "36") (name "Net-(Q1-B)") (class "Default")
      (node (ref "Q1") (pin "1") (pinfunction "B_1") (pintype "passive"))
      (node (ref "R7") (pin "2") (pinfunction "2_2") (pintype "passive"))
      (node (ref "R9") (pin "2") (pinfunction "2_2") (pintype "passive"))
    )
    (net (code "37") (name "Net-(Q1-C)") (class "Default")
      (node (ref "BZ1") (pin "2") (pinfunction "2_2") (pintype "passive"))
      (node (ref "Q1") (pin "3") (pinfunction "C_3") (pintype "passive"))
    )
    (net (code "38") (name "Net-(Q2-B)") (class "Default")
      (node (ref "Q2") (pin "1") (pinfunction "B_1") (pintype "passive"))
      (node (ref "R10") (pin "2") (pinfunction "2_2") (pintype "passive"))
      (node (ref "R8") (pin "2") (pinfunction "2_2") (pintype "passive"))
    )
    (net (code "39") (name "Net-(Q3-B)") (class "Default")
      (node (ref "Q3") (pin "1") (pinfunction "B_1") (pintype "passive"))
      (node (ref "R16") (pin "2") (pinfunction "2_2") (pintype "passive"))
    )
    (net (code "40") (name "Net-(Q4-B)") (class "Default")
      (node (ref "Q4") (pin "1") (pinfunction "B_1") (pintype "passive"))
      (node (ref "R17") (pin "2") (pinfunction "2_2") (pintype "passive"))
    )
    (net (code "41") (name "Net-(R3-Pad2)") (class "Default")
      (node (ref "R3") (pin "2") (pinfunction "2_2") (pintype "passive"))
      (node (ref "SW2") (pin "1") (pinfunction "1_1") (pintype "passive"))
    )
    (net (code "42") (name "Net-(R4-Pad2)") (class "Default")
      (node (ref "R4") (pin "2") (pinfunction "2_2") (pintype "passive"))
      (node (ref "SW3") (pin "1") (pinfunction "1_1") (pintype "passive"))
    )
    (net (code "43") (name "Net-(R6-Pad2)") (class "Default")
      (node (ref "R6") (pin "2") (pinfunction "2_2") (pintype "passive"))
      (node (ref "SW1") (pin "1") (pinfunction "1_1") (pintype "passive"))
      (node (ref "SW1") (pin "2") (pinfunction "2_2") (pintype "passive"))
    )
    (net (code "44") (name "Net-(U3-VBUS)") (class "Default")
      (node (ref "D9") (pin "2") (pinfunction "Cathode_2") (pintype "passive"))
      (node (ref "R12") (pin "1") (pinfunction "1_1") (pintype "passive"))
      (node (ref "R18") (pin "2") (pinfunction "2_2") (pintype "passive"))
      (node (ref "U3") (pin "8") (pinfunction "VBUS_8") (pintype "input"))
    )
    (net (code "45") (name "Net-(U3-~{RSTb})") (class "Default")
      (node (ref "R13") (pin "1") (pinfunction "1_1") (pintype "passive"))
      (node (ref "U3") (pin "9") (pinfunction "~{RSTb}_9") (pintype "input"))
    )
    (net (code "46") (name "Net-(U3-~{SUSPENDb})") (class "Default")
      (node (ref "R19") (pin "2") (pinfunction "2_2") (pintype "passive"))
      (node (ref "U3") (pin "11") (pinfunction "~{SUSPENDb}_11") (pintype "output"))
    )
    (net (code "47") (name "unconnected-(D4-A-Pad2)") (class "Default")
      (node (ref "D4") (pin "2") (pinfunction "A_2") (pintype "passive"))
    )
    (net (code "48") (name "unconnected-(D4-K-Pad1)") (class "Default")
      (node (ref "D4") (pin "1") (pinfunction "K_1") (pintype "passive"))
    )
    (net (code "49") (name "unconnected-(D5-A-Pad2)") (class "Default")
      (node (ref "D5") (pin "2") (pinfunction "A_2") (pintype "passive"))
    )
    (net (code "50") (name "unconnected-(D5-K-Pad1)") (class "Default")
      (node (ref "D5") (pin "1") (pinfunction "K_1") (pintype "passive"))
    )
    (net (code "51") (name "unconnected-(D6-A-Pad2)") (class "Default")
      (node (ref "D6") (pin "2") (pinfunction "A_2") (pintype "passive"))
    )
    (net (code "52") (name "unconnected-(D6-K-Pad1)") (class "Default")
      (node (ref "D6") (pin "1") (pinfunction "K_1") (pintype "passive"))
    )
    (net (code "53") (name "unconnected-(D7-A-Pad2)") (class "Default")
      (node (ref "D7") (pin "2") (pinfunction "A_2") (pintype "passive"))
    )
    (net (code "54") (name "unconnected-(D7-Dout-Pad2)") (class "Default")
      (node (ref "D7") (pin "2") (pinfunction "Dout_2") (pintype "output+no_connect"))
    )
    (net (code "55") (name "unconnected-(D7-K-Pad1)") (class "Default")
      (node (ref "D7") (pin "1") (pinfunction "K_1") (pintype "passive"))
    )
    (net (code "56") (name "unconnected-(M1-GND-Pad1)") (class "Default")
      (node (ref "M1") (pin "1") (pinfunction "GND_1") (pintype "power_in+no_connect"))
    )
    (net (code "57") (name "unconnected-(M1-SCL-Pad4)") (class "Default")
      (node (ref "M1") (pin "4") (pinfunction "SCL_4") (pintype "bidirectional+no_connect"))
    )
    (net (code "58") (name "unconnected-(M1-SDA-Pad3)") (class "Default")
      (node (ref "M1") (pin "3") (pinfunction "SDA_3") (pintype "bidirectional+no_connect"))
    )
    (net (code "59") (name "unconnected-(M1-VCC-Pad2)") (class "Default")
      (node (ref "M1") (pin "2") (pinfunction "VCC_2") (pintype "power_in+no_connect"))
    )
    (net (code "60") (name "unconnected-(U1-IO2-Pad24)") (class "Default")
      (node (ref "U1") (pin "24") (pinfunction "IO2_24") (pintype "bidirectional+no_connect"))
    )
    (net (code "61") (name "unconnected-(U1-IO5-Pad29)") (class "Default")
      (node (ref "U1") (pin "29") (pinfunction "IO5_29") (pintype "bidirectional+no_connect"))
    )
    (net (code "62") (name "unconnected-(U1-IO15-Pad23)") (class "Default")
      (node (ref "U1") (pin "23") (pinfunction "IO15_23") (pintype "bidirectional+no_connect"))
    )
    (net (code "63") (name "unconnected-(U1-IO17-Pad28)") (class "Default")
      (node (ref "U1") (pin "28") (pinfunction "IO17_28") (pintype "bidirectional+no_connect"))
    )
    (net (code "64") (name "unconnected-(U1-IO22-Pad36)") (class "Default")
      (node (ref "U1") (pin "36") (pinfunction "IO22_36") (pintype "bidirectional+no_connect"))
    )
    (net (code "65") (name "unconnected-(U1-IO23-Pad37)") (class "Default")
      (node (ref "U1") (pin "37") (pinfunction "IO23_37") (pintype "bidirectional+no_connect"))
    )
    (net (code "66") (name "unconnected-(U1-IO27-Pad12)") (class "Default")
      (node (ref "U1") (pin "12") (pinfunction "IO27_12") (pintype "bidirectional+no_connect"))
    )
    (net (code "67") (name "unconnected-(U1-IO32-Pad8)") (class "Default")
      (node (ref "U1") (pin "8") (pinfunction "IO32_8") (pintype "bidirectional+no_connect"))
    )
    (net (code "68") (name "unconnected-(U1-IO33-Pad9)") (class "Default")
      (node (ref "U1") (pin "9") (pinfunction "IO33_9") (pintype "bidirectional+no_connect"))
    )
    (net (code "69") (name "unconnected-(U1-IO34-Pad6)") (class "Default")
      (node (ref "U1") (pin "6") (pinfunction "IO34_6") (pintype "bidirectional+no_connect"))
    )
    (net (code "70") (name "unconnected-(U1-IO35-Pad7)") (class "Default")
      (node (ref "U1") (pin "7") (pinfunction "IO35_7") (pintype "bidirectional+no_connect"))
    )
    (net (code "71") (name "unconnected-(U1-SCL{slash}CLK-Pad20)") (class "Default")
      (node (ref "U1") (pin "20") (pinfunction "SCL/CLK_20") (pintype "bidirectional+no_connect"))
    )
    (net (code "72") (name "unconnected-(U1-SCS{slash}CMD-Pad19)") (class "Default")
      (node (ref "U1") (pin "19") (pinfunction "SCS/CMD_19") (pintype "bidirectional+no_connect"))
    )
    (net (code "73") (name "unconnected-(U1-SDI{slash}SD1-Pad22)") (class "Default")
      (node (ref "U1") (pin "22") (pinfunction "SDI/SD1_22") (pintype "bidirectional+no_connect"))
    )
    (net (code "74") (name "unconnected-(U1-SDO{slash}SD0-Pad21)") (class "Default")
      (node (ref "U1") (pin "21") (pinfunction "SDO/SD0_21") (pintype "bidirectional+no_connect"))
    )
    (net (code "75") (name "unconnected-(U1-SENSOR_VN-Pad5)") (class "Default")
      (node (ref "U1") (pin "5") (pinfunction "SENSOR_VN_5") (pintype "input+no_connect"))
    )
    (net (code "76") (name "unconnected-(U1-SENSOR_VP-Pad4)") (class "Default")
      (node (ref "U1") (pin "4") (pinfunction "SENSOR_VP_4") (pintype "input+no_connect"))
    )
    (net (code "77") (name "unconnected-(U1-SHD{slash}SD2-Pad17)") (class "Default")
      (node (ref "U1") (pin "17") (pinfunction "SHD/SD2_17") (pintype "bidirectional+no_connect"))
    )
    (net (code "78") (name "unconnected-(U1-SWP{slash}SD3-Pad18)") (class "Default")
      (node (ref "U1") (pin "18") (pinfunction "SWP/SD3_18") (pintype "bidirectional+no_connect"))
    )
    (net (code "79") (name "unconnected-(U3-CHR0-Pad15)") (class "Default")
      (node (ref "U3") (pin "15") (pinfunction "CHR0_15") (pintype "output+no_connect"))
    )
    (net (code "80") (name "unconnected-(U3-CHR1-Pad14)") (class "Default")
      (node (ref "U3") (pin "14") (pinfunction "CHR1_14") (pintype "output+no_connect"))
    )
    (net (code "81") (name "unconnected-(U3-CHREN-Pad13)") (class "Default")
      (node (ref "U3") (pin "13") (pinfunction "CHREN_13") (pintype "output+no_connect"))
    )
    (net (code "82") (name "unconnected-(U3-GPIO.2{slash}RS485-Pad17)") (class "Default")
      (node (ref "U3") (pin "17") (pinfunction "GPIO.2/RS485_17") (pintype "bidirectional+no_connect"))
    )
    (net (code "83") (name "unconnected-(U3-GPIO.3{slash}WAKEUP-Pad16)") (class "Default")
      (node (ref "U3") (pin "16") (pinfunction "GPIO.3/WAKEUP_16") (pintype "bidirectional+no_connect"))
    )
    (net (code "84") (name "unconnected-(U3-GPIO.4-Pad22)") (class "Default")
      (node (ref "U3") (pin "22") (pinfunction "GPIO.4_22") (pintype "bidirectional+no_connect"))
    )
    (net (code "85") (name "unconnected-(U3-GPIO.5-Pad21)") (class "Default")
      (node (ref "U3") (pin "21") (pinfunction "GPIO.5_21") (pintype "bidirectional+no_connect"))
    )
    (net (code "86") (name "unconnected-(U3-GPIO.6-Pad20)") (class "Default")
      (node (ref "U3") (pin "20") (pinfunction "GPIO.6_20") (pintype "bidirectional+no_connect"))
    )
    (net (code "87") (name "unconnected-(U3-NC-Pad10)") (class "Default")
      (node (ref "U3") (pin "10") (pinfunction "NC_10") (pintype "passive+no_connect"))
    )
    (net (code "88") (name "unconnected-(U3-SUSPEND-Pad12)") (class "Default")
      (node (ref "U3") (pin "12") (pinfunction "SUSPEND_12") (pintype "output+no_connect"))
    )
    (net (code "89") (name "unconnected-(U3-~{CTS}-Pad23)") (class "Default")
      (node (ref "U3") (pin "23") (pinfunction "~{CTS}_23") (pintype "input+no_connect"))
    )
    (net (code "90") (name "unconnected-(U3-~{DCD}-Pad1)") (class "Default")
      (node (ref "U3") (pin "1") (pinfunction "~{DCD}_1") (pintype "input+no_connect"))
    )
    (net (code "91") (name "unconnected-(U3-~{DSR}-Pad27)") (class "Default")
      (node (ref "U3") (pin "27") (pinfunction "~{DSR}_27") (pintype "input+no_connect"))
    )
    (net (code "92") (name "unconnected-(U3-~{RI}{slash}CLK-Pad2)") (class "Default")
      (node (ref "U3") (pin "2") (pinfunction "~{RI}/CLK_2") (pintype "bidirectional+no_connect"))
    )
  )
)
